# AirCond_P0_V2_0.net
KiCad netlist of a schematic drawn in Altium Designer
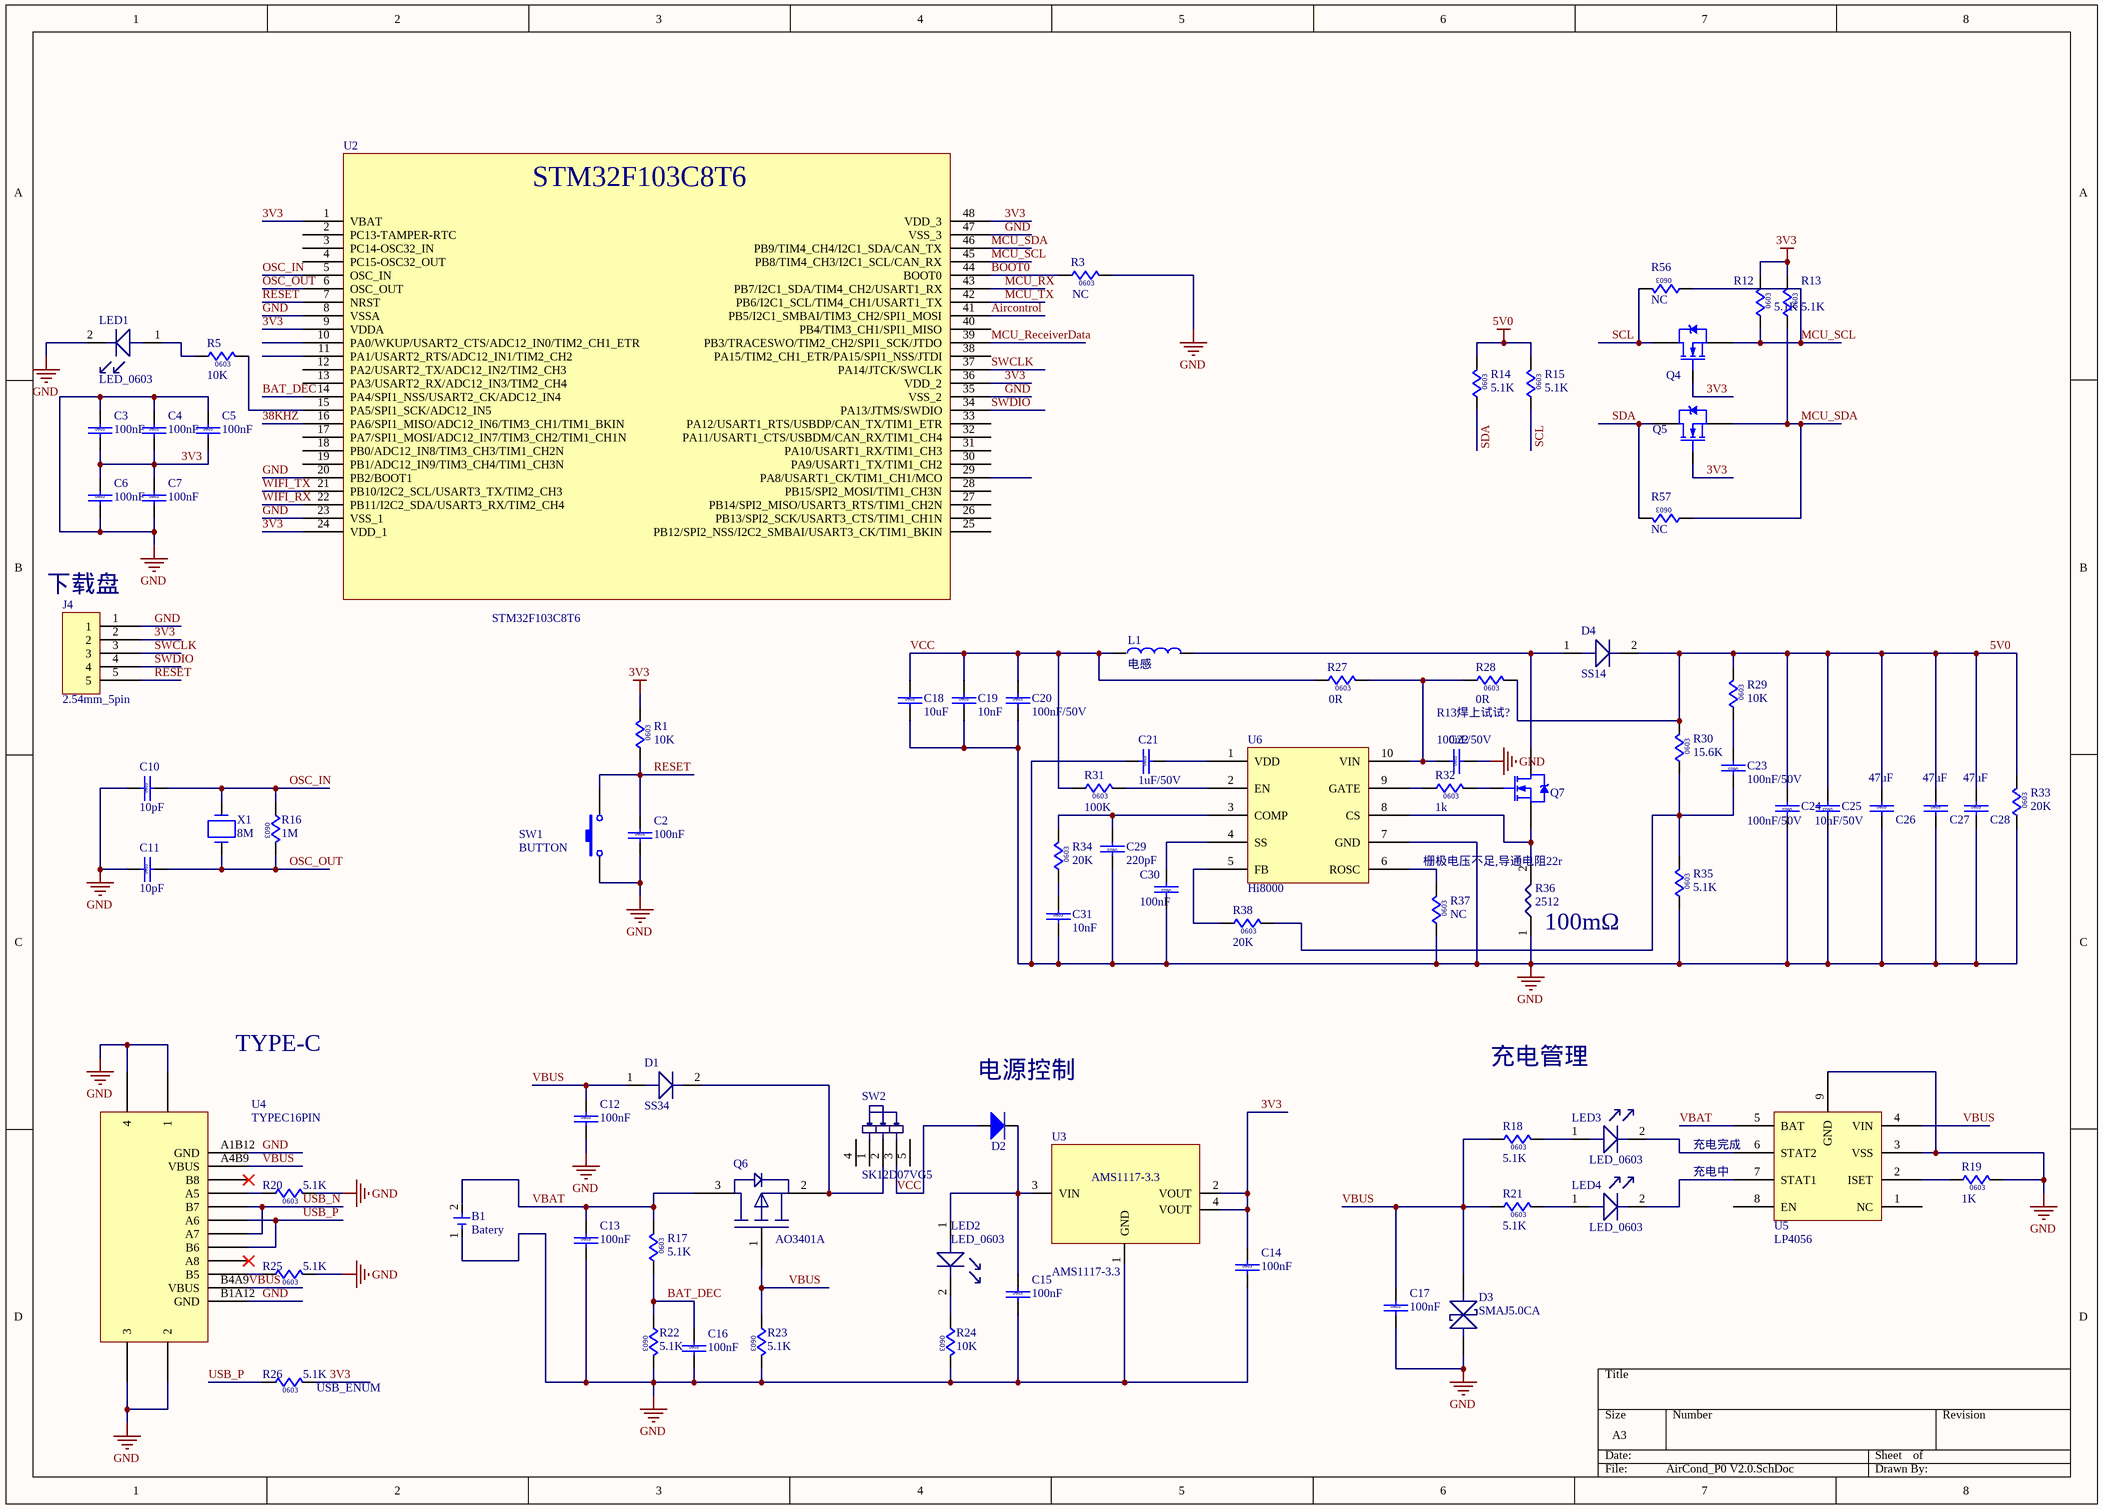
[diagram p0: AirCond_P0 V2.0.SchDoc]

(export (version "E")
  (design (tool "Eeschema 10.0.6"))
  (components
    (comp (ref "B1") (value "Batery") (footprint "BateryBox") (libsource (lib "ZWC") (part "Batery")))
    (comp (ref "C2") (value "100nF") (footprint "0603/CAP") (libsource (lib "ZWC") (part "CAP/0603")))
    (comp (ref "C3") (value "100nF") (footprint "0603/CAP") (libsource (lib "ZWC") (part "CAP/0603")))
    (comp (ref "C4") (value "100nF") (footprint "0603/CAP") (libsource (lib "ZWC") (part "CAP/0603")))
    (comp (ref "C5") (value "100nF") (footprint "0603/CAP") (libsource (lib "ZWC") (part "CAP/0603")))
    (comp (ref "C6") (value "100nF") (footprint "0603/CAP") (libsource (lib "ZWC") (part "CAP/0603")))
    (comp (ref "C7") (value "100nF") (footprint "0603/CAP") (libsource (lib "ZWC") (part "CAP/0603")))
    (comp (ref "C10") (value "10pF") (footprint "0603/CAP") (libsource (lib "ZWC") (part "CAP/0603")))
    (comp (ref "C11") (value "10pF") (footprint "0603/CAP") (libsource (lib "ZWC") (part "CAP/0603")))
    (comp (ref "C12") (value "100nF") (footprint "0603/CAP") (libsource (lib "ZWC") (part "CAP/0603")))
    (comp (ref "C13") (value "100nF") (footprint "0603/CAP") (libsource (lib "ZWC") (part "CAP/0603")))
    (comp (ref "C14") (value "100nF") (footprint "0603/CAP") (libsource (lib "ZWC") (part "CAP/0603")))
    (comp (ref "C15") (value "100nF") (footprint "0603/CAP") (libsource (lib "ZWC") (part "CAP/0603")))
    (comp (ref "C16") (value "100nF") (footprint "0603/CAP") (libsource (lib "ZWC") (part "CAP/0603")))
    (comp (ref "C17") (value "100nF") (footprint "0603/CAP") (libsource (lib "ZWC") (part "CAP/0603")))
    (comp (ref "C18") (value "10uF") (footprint "0603/CAP") (libsource (lib "ZWC") (part "CAP/0603")))
    (comp (ref "C19") (value "10nF") (footprint "0603/CAP") (libsource (lib "ZWC") (part "CAP/0603")))
    (comp (ref "C20") (value "100nF/50V") (footprint "0603/CAP") (libsource (lib "ZWC") (part "CAP/0603")))
    (comp (ref "C21") (value "1uF/50V") (footprint "0603/CAP") (libsource (lib "ZWC") (part "CAP/0603")))
    (comp (ref "C22") (value "100nF/50V") (footprint "0603/CAP") (libsource (lib "ZWC") (part "CAP/0603")))
    (comp (ref "C23") (value "100nF/50V") (footprint "0603/CAP") (libsource (lib "ZWC") (part "CAP/0603")))
    (comp (ref "C24") (value "100nF/50V") (footprint "0603/CAP") (libsource (lib "ZWC") (part "CAP/0603")))
    (comp (ref "C25") (value "10nF/50V") (footprint "0603/CAP") (libsource (lib "ZWC") (part "CAP/0603")))
    (comp (ref "C26") (value "47uF") (footprint "0805 - CAP") (libsource (lib "ZWC") (part "CAP/0805")))
    (comp (ref "C27") (value "47uF") (footprint "0805 - CAP") (libsource (lib "ZWC") (part "CAP/0805")))
    (comp (ref "C28") (value "47uF") (footprint "0805 - CAP") (libsource (lib "ZWC") (part "CAP/0805")))
    (comp (ref "C29") (value "220pF") (footprint "0603/CAP") (libsource (lib "ZWC") (part "CAP/0603")))
    (comp (ref "C30") (value "100nF") (footprint "0603/CAP") (libsource (lib "ZWC") (part "CAP/0603")))
    (comp (ref "C31") (value "10nF") (footprint "0603/CAP") (libsource (lib "ZWC") (part "CAP/0603")))
    (comp (ref "D1")
      (value "SS34")
      (footprint "SMA_L4.3-W2.6-LS5.0-RD")
      (libsource (lib "MySelf") (part "SS34"))
    )
    (comp (ref "D2") (value "S1MFL") (footprint "SOD-123Fl") (libsource (lib "ZWC") (part "S1MFL")))
    (comp (ref "D3")
      (value "SMAJ5.0CA")
      (footprint "DO-214AC(SMA)")
      (libsource (lib "MySelf") (part "SMAJ5.0CA"))
    )
    (comp (ref "D4")
      (value "SS14")
      (footprint "SMA_L4.3-W2.6-LS5.0-RD")
      (libsource (lib "MySelf") (part "SS34"))
    )
    (comp (ref "J4")
      (value "2.54mm_5pin")
      (footprint "2.54mm_5P")
      (libsource (lib "MySelf") (part "2.54mm_5pin"))
    )
    (comp (ref "L1") (value "电感") (footprint "SRP7028A-4R7") (libsource (lib "ZWC") (part "电感")))
    (comp (ref "LED1") (value "LED_0603") (footprint "0603/RES") (libsource (lib "MySelf") (part "LED_0603")))
    (comp (ref "LED2") (value "LED_0603") (footprint "0603/RES") (libsource (lib "MySelf") (part "LED_0603")))
    (comp (ref "LED3") (value "LED_0603") (footprint "0603/RES") (libsource (lib "MySelf") (part "LED_0603")))
    (comp (ref "LED4") (value "LED_0603") (footprint "0603/RES") (libsource (lib "MySelf") (part "LED_0603")))
    (comp (ref "Q4") (value "NMOS") (footprint "SOT-23") (libsource (lib "ZWC") (part "N-MOSE")))
    (comp (ref "Q5") (value "NMOS") (footprint "SOT-23") (libsource (lib "ZWC") (part "N-MOSE")))
    (comp (ref "Q6") (value "AO3401A") (footprint "SOT-23") (libsource (lib "MySelf") (part "AO3401A")))
    (comp (ref "Q7") (value "NMOS") (footprint "SOT-23") (libsource (lib "ZWC") (part "N-MOSE")))
    (comp (ref "R1") (value "10K") (footprint "0603/RES") (libsource (lib "ZWC") (part "RES/0603")))
    (comp (ref "R3") (value "NC") (footprint "0603/RES") (libsource (lib "ZWC") (part "RES/0603")))
    (comp (ref "R5") (value "10K") (footprint "0603/RES") (libsource (lib "ZWC") (part "RES/0603")))
    (comp (ref "R12") (value "5.1K") (footprint "0603/RES") (libsource (lib "ZWC") (part "RES/0603")))
    (comp (ref "R13") (value "5.1K") (footprint "0603/RES") (libsource (lib "ZWC") (part "RES/0603")))
    (comp (ref "R14") (value "5.1K") (footprint "0603/RES") (libsource (lib "ZWC") (part "RES/0603")))
    (comp (ref "R15") (value "5.1K") (footprint "0603/RES") (libsource (lib "ZWC") (part "RES/0603")))
    (comp (ref "R16") (value "1M") (footprint "0603/RES") (libsource (lib "ZWC") (part "RES/0603")))
    (comp (ref "R17") (value "5.1K") (footprint "0603/RES") (libsource (lib "ZWC") (part "RES/0603")))
    (comp (ref "R18") (value "5.1K") (footprint "0603/RES") (libsource (lib "ZWC") (part "RES/0603")))
    (comp (ref "R19") (value "1K") (footprint "0603/RES") (libsource (lib "ZWC") (part "RES/0603")))
    (comp (ref "R20") (value "5.1K") (footprint "0603/RES") (libsource (lib "ZWC") (part "RES/0603")))
    (comp (ref "R21") (value "5.1K") (footprint "0603/RES") (libsource (lib "ZWC") (part "RES/0603")))
    (comp (ref "R22") (value "5.1K") (footprint "0603/RES") (libsource (lib "ZWC") (part "RES/0603")))
    (comp (ref "R23") (value "5.1K") (footprint "0603/RES") (libsource (lib "ZWC") (part "RES/0603")))
    (comp (ref "R24") (value "10K") (footprint "0603/RES") (libsource (lib "ZWC") (part "RES/0603")))
    (comp (ref "R25") (value "5.1K") (footprint "0603/RES") (libsource (lib "ZWC") (part "RES/0603")))
    (comp (ref "R26") (value "5.1K") (footprint "0603/RES") (libsource (lib "ZWC") (part "RES/0603")))
    (comp (ref "R27") (value "0R") (footprint "0603/RES") (libsource (lib "ZWC") (part "RES/0603")))
    (comp (ref "R28") (value "0R") (footprint "0603/RES") (libsource (lib "ZWC") (part "RES/0603")))
    (comp (ref "R29") (value "10K") (footprint "0603/RES") (libsource (lib "ZWC") (part "RES/0603")))
    (comp (ref "R30") (value "15.6K") (footprint "0603/RES") (libsource (lib "ZWC") (part "RES/0603")))
    (comp (ref "R31") (value "100K") (footprint "0603/RES") (libsource (lib "ZWC") (part "RES/0603")))
    (comp (ref "R32") (value "1k") (footprint "0603/RES") (libsource (lib "ZWC") (part "RES/0603")))
    (comp (ref "R33") (value "20K") (footprint "0603/RES") (libsource (lib "ZWC") (part "RES/0603")))
    (comp (ref "R34") (value "20K") (footprint "0603/RES") (libsource (lib "ZWC") (part "RES/0603")))
    (comp (ref "R35") (value "5.1K") (footprint "0603/RES") (libsource (lib "ZWC") (part "RES/0603")))
    (comp (ref "R36") (value "2512") (footprint "2512") (libsource (lib "MySelf") (part "2512")))
    (comp (ref "R37") (value "NC") (footprint "0603/RES") (libsource (lib "ZWC") (part "RES/0603")))
    (comp (ref "R38") (value "20K") (footprint "0603/RES") (libsource (lib "ZWC") (part "RES/0603")))
    (comp (ref "R56") (value "NC") (footprint "0603/RES") (libsource (lib "ZWC") (part "RES/0603")))
    (comp (ref "R57") (value "NC") (footprint "0603/RES") (libsource (lib "ZWC") (part "RES/0603")))
    (comp (ref "SW1") (value "BUTTON") (footprint "Key-D8mm") (libsource (lib "ZWC") (part "BUTTON_1")))
    (comp (ref "SW2")
      (value "SK12D07VG5")
      (footprint "SK12D07VG5")
      (libsource (lib "MySelf") (part "SK12D07VG5"))
    )
    (comp (ref "U2")
      (value "STM32F103C8T6")
      (footprint "LQFP48-STM32")
      (description "STM32F103")
      (libsource (lib "MySelf") (part "STM32F103C8T6"))
    )
    (comp (ref "U3")
      (value "AMS1117-3.3")
      (footprint "AMS1117-3.3")
      (libsource (lib "ZWC") (part "AMS1117-3.3"))
    )
    (comp (ref "U4")
      (value "TYPEC16PIN")
      (footprint "Type-C 16PIN")
      (libsource (lib "MySelf") (part "TYPEC16PIN"))
    )
    (comp (ref "U5") (value "LP4056") (footprint "ESOP-8") (libsource (lib "MySelf") (part "LP4056")))
    (comp (ref "U6") (value "Hi8000") (footprint "ESSOP10") (libsource (lib "MySelf") (part "Hi8000")))
    (comp (ref "X1") (value "8M") (footprint "两脚晶振") (libsource (lib "ZWC") (part "两脚 晶振")))
  )
  (nets
    (net (code "1") (name "/38KHZ") (class "Default")
      (node (ref "U2") (pin "16") (pinfunction "PA6/SPI1_MISO/ADC12_IN6/TIM3_CH1/TIM1_BKIN_16") (pintype "passive"))
    )
    (net (code "2") (name "/Aircontrol") (class "Default")
      (node (ref "U2") (pin "41") (pinfunction "PB5/I2C1_SMBAI/TIM3_CH2/SPI1_MOSI_41") (pintype "passive"))
    )
    (net (code "3") (name "/BAT_DEC") (class "Default")
      (node (ref "C16") (pin "1") (pinfunction "1_1") (pintype "passive"))
      (node (ref "R17") (pin "1") (pinfunction "1_1") (pintype "passive"))
      (node (ref "R22") (pin "1") (pinfunction "1_1") (pintype "passive"))
      (node (ref "U2") (pin "14") (pinfunction "PA4/SPI1_NSS/USART2_CK/ADC12_IN4_14") (pintype "passive"))
    )
    (net (code "4") (name "/BOOT0") (class "Default")
      (node (ref "R3") (pin "1") (pinfunction "1_1") (pintype "passive"))
      (node (ref "U2") (pin "44") (pinfunction "BOOT0_44") (pintype "passive"))
    )
    (net (code "5") (name "/MCU_RX") (class "Default")
      (node (ref "U2") (pin "43") (pinfunction "PB7/I2C1_SDA/TIM4_CH2/USART1_RX_43") (pintype "passive"))
    )
    (net (code "6") (name "/MCU_ReceiverData") (class "Default")
      (node (ref "U2") (pin "39") (pinfunction "PB3/TRACESWO/TIM2_CH2/SPI1_SCK/JTDO_39") (pintype "passive"))
    )
    (net (code "7") (name "/MCU_SCL") (class "Default")
      (node (ref "Q4") (pin "2") (pinfunction "S_2") (pintype "passive"))
      (node (ref "R12") (pin "1") (pinfunction "1_1") (pintype "passive"))
      (node (ref "R56") (pin "1") (pinfunction "1_1") (pintype "passive"))
      (node (ref "U2") (pin "45") (pinfunction "PB8/TIM4_CH3/I2C1_SCL/CAN_RX_45") (pintype "passive"))
    )
    (net (code "8") (name "/MCU_SDA") (class "Default")
      (node (ref "Q5") (pin "2") (pinfunction "S_2") (pintype "passive"))
      (node (ref "R13") (pin "1") (pinfunction "1_1") (pintype "passive"))
      (node (ref "R57") (pin "1") (pinfunction "1_1") (pintype "passive"))
      (node (ref "U2") (pin "46") (pinfunction "PB9/TIM4_CH4/I2C1_SDA/CAN_TX_46") (pintype "passive"))
    )
    (net (code "9") (name "/MCU_TX") (class "Default")
      (node (ref "U2") (pin "42") (pinfunction "PB6/I2C1_SCL/TIM4_CH1/USART1_TX_42") (pintype "passive"))
    )
    (net (code "10") (name "/OSC_IN") (class "Default")
      (node (ref "C10") (pin "2") (pinfunction "2_2") (pintype "passive"))
      (node (ref "R16") (pin "1") (pinfunction "1_1") (pintype "passive"))
      (node (ref "U2") (pin "5") (pinfunction "OSC_IN_5") (pintype "passive"))
      (node (ref "X1") (pin "2") (pinfunction "2_2") (pintype "passive"))
    )
    (net (code "11") (name "/OSC_OUT") (class "Default")
      (node (ref "C11") (pin "2") (pinfunction "2_2") (pintype "passive"))
      (node (ref "R16") (pin "2") (pinfunction "2_2") (pintype "passive"))
      (node (ref "U2") (pin "6") (pinfunction "OSC_OUT_6") (pintype "passive"))
      (node (ref "X1") (pin "1") (pinfunction "1_1") (pintype "passive"))
    )
    (net (code "12") (name "/RESET") (class "Default")
      (node (ref "C2") (pin "1") (pinfunction "1_1") (pintype "passive"))
      (node (ref "J4") (pin "5") (pinfunction "5_5") (pintype "passive"))
      (node (ref "R1") (pin "1") (pinfunction "1_1") (pintype "passive"))
      (node (ref "SW1") (pin "2") (pinfunction "2_2") (pintype "passive"))
      (node (ref "U2") (pin "7") (pinfunction "NRST_7") (pintype "passive"))
    )
    (net (code "13") (name "/SCL") (class "Default")
      (node (ref "Q4") (pin "3") (pinfunction "D_3") (pintype "passive"))
      (node (ref "R15") (pin "1") (pinfunction "1_1") (pintype "passive"))
      (node (ref "R56") (pin "2") (pinfunction "2_2") (pintype "passive"))
    )
    (net (code "14") (name "/SDA") (class "Default")
      (node (ref "Q5") (pin "3") (pinfunction "D_3") (pintype "passive"))
      (node (ref "R14") (pin "1") (pinfunction "1_1") (pintype "passive"))
      (node (ref "R57") (pin "2") (pinfunction "2_2") (pintype "passive"))
    )
    (net (code "15") (name "/SWCLK") (class "Default")
      (node (ref "J4") (pin "3") (pinfunction "3_3") (pintype "passive"))
      (node (ref "U2") (pin "37") (pinfunction "PA14/JTCK/SWCLK_37") (pintype "passive"))
    )
    (net (code "16") (name "/SWDIO") (class "Default")
      (node (ref "J4") (pin "4") (pinfunction "4_4") (pintype "passive"))
      (node (ref "U2") (pin "34") (pinfunction "PA13/JTMS/SWDIO_34") (pintype "passive"))
    )
    (net (code "17") (name "/USB_N") (class "Default")
      (node (ref "U4") (pin "A7") (pinfunction "A7_A7") (pintype "passive"))
      (node (ref "U4") (pin "B7") (pinfunction "B7_B7") (pintype "passive"))
    )
    (net (code "18") (name "/USB_P") (class "Default")
      (node (ref "R26") (pin "1") (pinfunction "1_1") (pintype "passive"))
      (node (ref "U4") (pin "A6") (pinfunction "A6_A6") (pintype "passive"))
      (node (ref "U4") (pin "B6") (pinfunction "B6_B6") (pintype "passive"))
    )
    (net (code "19") (name "/VBAT") (class "Default")
      (node (ref "B1") (pin "2") (pinfunction "+_2") (pintype "passive"))
      (node (ref "C13") (pin "1") (pinfunction "1_1") (pintype "passive"))
      (node (ref "Q6") (pin "3") (pinfunction "3_3") (pintype "passive"))
      (node (ref "R17") (pin "2") (pinfunction "2_2") (pintype "passive"))
      (node (ref "U5") (pin "5") (pinfunction "BAT_5") (pintype "passive"))
    )
    (net (code "20") (name "/VBUS") (class "Default")
      (node (ref "C12") (pin "1") (pinfunction "1_1") (pintype "passive"))
      (node (ref "C17") (pin "1") (pinfunction "1_1") (pintype "passive"))
      (node (ref "D1") (pin "1") (pinfunction "1_1") (pintype "passive"))
      (node (ref "D3") (pin "1") (pinfunction "1_1") (pintype "passive"))
      (node (ref "Q6") (pin "1") (pinfunction "1_1") (pintype "passive"))
      (node (ref "R18") (pin "1") (pinfunction "1_1") (pintype "passive"))
      (node (ref "R21") (pin "1") (pinfunction "1_1") (pintype "passive"))
      (node (ref "R23") (pin "1") (pinfunction "1_1") (pintype "passive"))
      (node (ref "U4") (pin "A4B9") (pinfunction "VBUS_A4B9") (pintype "passive"))
      (node (ref "U4") (pin "B4A9") (pinfunction "VBUS_B4A9") (pintype "passive"))
      (node (ref "U5") (pin "4") (pinfunction "VIN_4") (pintype "passive"))
    )
    (net (code "21") (name "/VCC") (class "Default")
      (node (ref "C18") (pin "1") (pinfunction "1_1") (pintype "passive"))
      (node (ref "C19") (pin "1") (pinfunction "1_1") (pintype "passive"))
      (node (ref "C20") (pin "1") (pinfunction "1_1") (pintype "passive"))
      (node (ref "D2") (pin "1") (pintype "passive"))
      (node (ref "L1") (pin "1") (pinfunction "1_1") (pintype "passive"))
      (node (ref "R27") (pin "1") (pinfunction "1_1") (pintype "passive"))
      (node (ref "R31") (pin "1") (pinfunction "1_1") (pintype "passive"))
      (node (ref "SW2") (pin "3") (pinfunction "3_3") (pintype "passive"))
    )
    (net (code "22") (name "/WIFI_RX") (class "Default")
      (node (ref "U2") (pin "22") (pinfunction "PB11/I2C2_SDA/USART3_RX/TIM2_CH4_22") (pintype "passive"))
    )
    (net (code "23") (name "/WIFI_TX") (class "Default")
      (node (ref "U2") (pin "21") (pinfunction "PB10/I2C2_SCL/USART3_TX/TIM2_CH3_21") (pintype "passive"))
    )
    (net (code "24") (name "3V3") (class "Default")
      (node (ref "C14") (pin "1") (pinfunction "1_1") (pintype "passive"))
      (node (ref "C3") (pin "2") (pinfunction "2_2") (pintype "passive"))
      (node (ref "C4") (pin "2") (pinfunction "2_2") (pintype "passive"))
      (node (ref "C5") (pin "2") (pinfunction "2_2") (pintype "passive"))
      (node (ref "C6") (pin "1") (pinfunction "1_1") (pintype "passive"))
      (node (ref "C7") (pin "1") (pinfunction "1_1") (pintype "passive"))
      (node (ref "J4") (pin "2") (pinfunction "2_2") (pintype "passive"))
      (node (ref "Q4") (pin "1") (pinfunction "G_1") (pintype "passive"))
      (node (ref "Q5") (pin "1") (pinfunction "G_1") (pintype "passive"))
      (node (ref "R1") (pin "2") (pinfunction "2_2") (pintype "passive"))
      (node (ref "R12") (pin "2") (pinfunction "2_2") (pintype "passive"))
      (node (ref "R13") (pin "2") (pinfunction "2_2") (pintype "passive"))
      (node (ref "R26") (pin "2") (pinfunction "2_2") (pintype "passive"))
      (node (ref "U2") (pin "1") (pinfunction "VBAT_1") (pintype "passive"))
      (node (ref "U2") (pin "24") (pinfunction "VDD_1_24") (pintype "passive"))
      (node (ref "U2") (pin "36") (pinfunction "VDD_2_36") (pintype "passive"))
      (node (ref "U2") (pin "48") (pinfunction "VDD_3_48") (pintype "passive"))
      (node (ref "U2") (pin "9") (pinfunction "VDDA_9") (pintype "passive"))
      (node (ref "U3") (pin "2") (pinfunction "VOUT_2") (pintype "passive"))
      (node (ref "U3") (pin "4") (pinfunction "VOUT_4") (pintype "passive"))
    )
    (net (code "25") (name "5V0") (class "Default")
      (node (ref "C24") (pin "2") (pinfunction "2_2") (pintype "passive"))
      (node (ref "C25") (pin "2") (pinfunction "2_2") (pintype "passive"))
      (node (ref "C26") (pin "1") (pinfunction "1_1") (pintype "passive"))
      (node (ref "C27") (pin "1") (pinfunction "1_1") (pintype "passive"))
      (node (ref "C28") (pin "1") (pinfunction "1_1") (pintype "passive"))
      (node (ref "D4") (pin "2") (pinfunction "2_2") (pintype "passive"))
      (node (ref "R14") (pin "2") (pinfunction "2_2") (pintype "passive"))
      (node (ref "R15") (pin "2") (pinfunction "2_2") (pintype "passive"))
      (node (ref "R28") (pin "2") (pinfunction "2_2") (pintype "passive"))
      (node (ref "R29") (pin "2") (pinfunction "2_2") (pintype "passive"))
      (node (ref "R30") (pin "2") (pinfunction "2_2") (pintype "passive"))
      (node (ref "R33") (pin "2") (pinfunction "2_2") (pintype "passive"))
    )
    (net (code "26") (name "GND") (class "Default")
      (node (ref "B1") (pin "1") (pinfunction "-_1") (pintype "passive"))
      (node (ref "C10") (pin "1") (pinfunction "1_1") (pintype "passive"))
      (node (ref "C11") (pin "1") (pinfunction "1_1") (pintype "passive"))
      (node (ref "C12") (pin "2") (pinfunction "2_2") (pintype "passive"))
      (node (ref "C13") (pin "2") (pinfunction "2_2") (pintype "passive"))
      (node (ref "C14") (pin "2") (pinfunction "2_2") (pintype "passive"))
      (node (ref "C15") (pin "2") (pinfunction "2_2") (pintype "passive"))
      (node (ref "C16") (pin "2") (pinfunction "2_2") (pintype "passive"))
      (node (ref "C17") (pin "2") (pinfunction "2_2") (pintype "passive"))
      (node (ref "C18") (pin "2") (pinfunction "2_2") (pintype "passive"))
      (node (ref "C19") (pin "2") (pinfunction "2_2") (pintype "passive"))
      (node (ref "C2") (pin "2") (pinfunction "2_2") (pintype "passive"))
      (node (ref "C20") (pin "2") (pinfunction "2_2") (pintype "passive"))
      (node (ref "C21") (pin "1") (pinfunction "1_1") (pintype "passive"))
      (node (ref "C22") (pin "2") (pinfunction "2_2") (pintype "passive"))
      (node (ref "C24") (pin "1") (pinfunction "1_1") (pintype "passive"))
      (node (ref "C25") (pin "1") (pinfunction "1_1") (pintype "passive"))
      (node (ref "C26") (pin "2") (pinfunction "2_2") (pintype "passive"))
      (node (ref "C27") (pin "2") (pinfunction "2_2") (pintype "passive"))
      (node (ref "C28") (pin "2") (pinfunction "2_2") (pintype "passive"))
      (node (ref "C29") (pin "1") (pinfunction "1_1") (pintype "passive"))
      (node (ref "C3") (pin "1") (pinfunction "1_1") (pintype "passive"))
      (node (ref "C30") (pin "1") (pinfunction "1_1") (pintype "passive"))
      (node (ref "C31") (pin "2") (pinfunction "2_2") (pintype "passive"))
      (node (ref "C4") (pin "1") (pinfunction "1_1") (pintype "passive"))
      (node (ref "C5") (pin "1") (pinfunction "1_1") (pintype "passive"))
      (node (ref "C6") (pin "2") (pinfunction "2_2") (pintype "passive"))
      (node (ref "C7") (pin "2") (pinfunction "2_2") (pintype "passive"))
      (node (ref "D3") (pin "2") (pinfunction "2_2") (pintype "passive"))
      (node (ref "J4") (pin "1") (pinfunction "1_1") (pintype "passive"))
      (node (ref "LED1") (pin "2") (pinfunction "2_2") (pintype "passive"))
      (node (ref "R19") (pin "2") (pinfunction "2_2") (pintype "passive"))
      (node (ref "R20") (pin "2") (pinfunction "2_2") (pintype "passive"))
      (node (ref "R22") (pin "2") (pinfunction "2_2") (pintype "passive"))
      (node (ref "R23") (pin "2") (pinfunction "2_2") (pintype "passive"))
      (node (ref "R24") (pin "2") (pinfunction "2_2") (pintype "passive"))
      (node (ref "R25") (pin "2") (pinfunction "2_2") (pintype "passive"))
      (node (ref "R3") (pin "2") (pinfunction "2_2") (pintype "passive"))
      (node (ref "R33") (pin "1") (pinfunction "1_1") (pintype "passive"))
      (node (ref "R35") (pin "1") (pinfunction "1_1") (pintype "passive"))
      (node (ref "R36") (pin "1") (pinfunction "1_1") (pintype "passive"))
      (node (ref "R37") (pin "1") (pinfunction "1_1") (pintype "passive"))
      (node (ref "SW1") (pin "1") (pinfunction "1_1") (pintype "passive"))
      (node (ref "U2") (pin "20") (pinfunction "PB2/BOOT1_20") (pintype "passive"))
      (node (ref "U2") (pin "23") (pinfunction "VSS_1_23") (pintype "passive"))
      (node (ref "U2") (pin "35") (pinfunction "VSS_2_35") (pintype "passive"))
      (node (ref "U2") (pin "47") (pinfunction "VSS_3_47") (pintype "passive"))
      (node (ref "U2") (pin "8") (pinfunction "VSSA_8") (pintype "passive"))
      (node (ref "U3") (pin "1") (pinfunction "GND_1") (pintype "passive"))
      (node (ref "U4") (pin "1") (pinfunction "1_1") (pintype "passive"))
      (node (ref "U4") (pin "2") (pinfunction "2_2") (pintype "passive"))
      (node (ref "U4") (pin "3") (pinfunction "3_3") (pintype "passive"))
      (node (ref "U4") (pin "4") (pinfunction "4_4") (pintype "passive"))
      (node (ref "U4") (pin "A1B12") (pinfunction "GND_A1B12") (pintype "passive"))
      (node (ref "U4") (pin "B1A12") (pinfunction "GND_B1A12") (pintype "passive"))
      (node (ref "U5") (pin "3") (pinfunction "VSS_3") (pintype "passive"))
      (node (ref "U5") (pin "9") (pinfunction "GND_9") (pintype "passive"))
      (node (ref "U6") (pin "7") (pinfunction "GND_7") (pintype "passive"))
    )
    (net (code "27") (name "Net-(C23-Pad1)") (class "Default")
      (node (ref "C23") (pin "1") (pinfunction "1_1") (pintype "passive"))
      (node (ref "R30") (pin "1") (pinfunction "1_1") (pintype "passive"))
      (node (ref "R35") (pin "2") (pinfunction "2_2") (pintype "passive"))
      (node (ref "R38") (pin "2") (pinfunction "2_2") (pintype "passive"))
    )
    (net (code "28") (name "Net-(C23-Pad2)") (class "Default")
      (node (ref "C23") (pin "2") (pinfunction "2_2") (pintype "passive"))
      (node (ref "R29") (pin "1") (pinfunction "1_1") (pintype "passive"))
    )
    (net (code "29") (name "Net-(C31-Pad1)") (class "Default")
      (node (ref "C31") (pin "1") (pinfunction "1_1") (pintype "passive"))
      (node (ref "R34") (pin "1") (pinfunction "1_1") (pintype "passive"))
    )
    (net (code "30") (name "Net-(D1-Pad2)") (class "Default")
      (node (ref "D1") (pin "2") (pinfunction "2_2") (pintype "passive"))
      (node (ref "Q6") (pin "2") (pinfunction "2_2") (pintype "passive"))
      (node (ref "SW2") (pin "2") (pinfunction "2_2") (pintype "passive"))
    )
    (net (code "31") (name "Net-(LED1-Pad1)") (class "Default")
      (node (ref "LED1") (pin "1") (pinfunction "1_1") (pintype "passive"))
      (node (ref "R5") (pin "1") (pinfunction "1_1") (pintype "passive"))
    )
    (net (code "32") (name "Net-(LED2-Pad2)") (class "Default")
      (node (ref "LED2") (pin "2") (pinfunction "2_2") (pintype "passive"))
      (node (ref "R24") (pin "1") (pinfunction "1_1") (pintype "passive"))
    )
    (net (code "33") (name "Net-(LED3-Pad1)") (class "Default")
      (node (ref "LED3") (pin "1") (pinfunction "1_1") (pintype "passive"))
      (node (ref "R18") (pin "2") (pinfunction "2_2") (pintype "passive"))
    )
    (net (code "34") (name "Net-(LED4-Pad1)") (class "Default")
      (node (ref "LED4") (pin "1") (pinfunction "1_1") (pintype "passive"))
      (node (ref "R21") (pin "2") (pinfunction "2_2") (pintype "passive"))
    )
    (net (code "35") (name "Net-(Q7-D)") (class "Default")
      (node (ref "D4") (pin "1") (pinfunction "1_1") (pintype "passive"))
      (node (ref "L1") (pin "2") (pinfunction "2_2") (pintype "passive"))
      (node (ref "Q7") (pin "3") (pinfunction "D_3") (pintype "passive"))
    )
    (net (code "36") (name "Net-(Q7-G)") (class "Default")
      (node (ref "Q7") (pin "1") (pinfunction "G_1") (pintype "passive"))
      (node (ref "R32") (pin "2") (pinfunction "2_2") (pintype "passive"))
    )
    (net (code "37") (name "Net-(Q7-S)") (class "Default")
      (node (ref "Q7") (pin "2") (pinfunction "S_2") (pintype "passive"))
      (node (ref "R36") (pin "2") (pinfunction "2_2") (pintype "passive"))
      (node (ref "U6") (pin "8") (pinfunction "CS_8") (pintype "passive"))
    )
    (net (code "38") (name "Net-(R20-Pad1)") (class "Default")
      (node (ref "R20") (pin "1") (pinfunction "1_1") (pintype "passive"))
      (node (ref "U4") (pin "A5") (pinfunction "A5_A5") (pintype "passive"))
    )
    (net (code "39") (name "Net-(R25-Pad1)") (class "Default")
      (node (ref "R25") (pin "1") (pinfunction "1_1") (pintype "passive"))
      (node (ref "U4") (pin "B5") (pinfunction "B5_B5") (pintype "passive"))
    )
    (net (code "40") (name "Net-(U2-PA5{slash}SPI1_SCK{slash}ADC12_IN5)") (class "Default")
      (node (ref "R5") (pin "2") (pinfunction "2_2") (pintype "passive"))
      (node (ref "U2") (pin "15") (pinfunction "PA5/SPI1_SCK/ADC12_IN5_15") (pintype "passive"))
    )
    (net (code "41") (name "Net-(U3-VIN)") (class "Default")
      (node (ref "C15") (pin "1") (pinfunction "1_1") (pintype "passive"))
      (node (ref "D2") (pin "2") (pintype "passive"))
      (node (ref "LED2") (pin "1") (pinfunction "1_1") (pintype "passive"))
      (node (ref "U3") (pin "3") (pinfunction "VIN_3") (pintype "passive"))
    )
    (net (code "42") (name "Net-(U5-ISET)") (class "Default")
      (node (ref "R19") (pin "1") (pinfunction "1_1") (pintype "passive"))
      (node (ref "U5") (pin "2") (pinfunction "ISET_2") (pintype "passive"))
    )
    (net (code "43") (name "Net-(U5-STAT1)") (class "Default")
      (node (ref "LED4") (pin "2") (pinfunction "2_2") (pintype "passive"))
      (node (ref "U5") (pin "7") (pinfunction "STAT1_7") (pintype "passive"))
    )
    (net (code "44") (name "Net-(U5-STAT2)") (class "Default")
      (node (ref "LED3") (pin "2") (pinfunction "2_2") (pintype "passive"))
      (node (ref "U5") (pin "6") (pinfunction "STAT2_6") (pintype "passive"))
    )
    (net (code "45") (name "Net-(U6-COMP)") (class "Default")
      (node (ref "C29") (pin "2") (pinfunction "2_2") (pintype "passive"))
      (node (ref "R34") (pin "2") (pinfunction "2_2") (pintype "passive"))
      (node (ref "U6") (pin "3") (pinfunction "COMP_3") (pintype "passive"))
    )
    (net (code "46") (name "Net-(U6-EN)") (class "Default")
      (node (ref "R31") (pin "2") (pinfunction "2_2") (pintype "passive"))
      (node (ref "U6") (pin "2") (pinfunction "EN_2") (pintype "passive"))
    )
    (net (code "47") (name "Net-(U6-FB)") (class "Default")
      (node (ref "R38") (pin "1") (pinfunction "1_1") (pintype "passive"))
      (node (ref "U6") (pin "5") (pinfunction "FB_5") (pintype "passive"))
    )
    (net (code "48") (name "Net-(U6-GATE)") (class "Default")
      (node (ref "R32") (pin "1") (pinfunction "1_1") (pintype "passive"))
      (node (ref "U6") (pin "9") (pinfunction "GATE_9") (pintype "passive"))
    )
    (net (code "49") (name "Net-(U6-ROSC)") (class "Default")
      (node (ref "R37") (pin "2") (pinfunction "2_2") (pintype "passive"))
      (node (ref "U6") (pin "6") (pinfunction "ROSC_6") (pintype "passive"))
    )
    (net (code "50") (name "Net-(U6-SS)") (class "Default")
      (node (ref "C30") (pin "2") (pinfunction "2_2") (pintype "passive"))
      (node (ref "U6") (pin "4") (pinfunction "SS_4") (pintype "passive"))
    )
    (net (code "51") (name "Net-(U6-VDD)") (class "Default")
      (node (ref "C21") (pin "2") (pinfunction "2_2") (pintype "passive"))
      (node (ref "U6") (pin "1") (pinfunction "VDD_1") (pintype "passive"))
    )
    (net (code "52") (name "Net-(U6-VIN)") (class "Default")
      (node (ref "C22") (pin "1") (pinfunction "1_1") (pintype "passive"))
      (node (ref "R27") (pin "2") (pinfunction "2_2") (pintype "passive"))
      (node (ref "R28") (pin "1") (pinfunction "1_1") (pintype "passive"))
      (node (ref "U6") (pin "10") (pinfunction "VIN_10") (pintype "passive"))
    )
    (net (code "53") (name "unconnected-(SW2-Pad1)") (class "Default")
      (node (ref "SW2") (pin "1") (pinfunction "1_1") (pintype "passive"))
    )
    (net (code "54") (name "unconnected-(SW2-Pad4)") (class "Default")
      (node (ref "SW2") (pin "4") (pinfunction "4_4") (pintype "passive"))
    )
    (net (code "55") (name "unconnected-(SW2-Pad5)") (class "Default")
      (node (ref "SW2") (pin "5") (pinfunction "5_5") (pintype "passive"))
    )
    (net (code "56") (name "unconnected-(U2-PA0{slash}WKUP{slash}USART2_CTS{slash}ADC12_IN0{slash}TIM2_CH1_ETR-Pad10)") (class "Default")
      (node (ref "U2") (pin "10") (pinfunction "PA0/WKUP/USART2_CTS/ADC12_IN0/TIM2_CH1_ETR_10") (pintype "passive"))
    )
    (net (code "57") (name "unconnected-(U2-PA1{slash}USART2_RTS{slash}ADC12_IN1{slash}TIM2_CH2-Pad11)") (class "Default")
      (node (ref "U2") (pin "11") (pinfunction "PA1/USART2_RTS/ADC12_IN1/TIM2_CH2_11") (pintype "passive"))
    )
    (net (code "58") (name "unconnected-(U2-PA2{slash}USART2_TX{slash}ADC12_IN2{slash}TIM2_CH3-Pad12)") (class "Default")
      (node (ref "U2") (pin "12") (pinfunction "PA2/USART2_TX/ADC12_IN2/TIM2_CH3_12") (pintype "passive"))
    )
    (net (code "59") (name "unconnected-(U2-PA3{slash}USART2_RX{slash}ADC12_IN3{slash}TIM2_CH4-Pad13)") (class "Default")
      (node (ref "U2") (pin "13") (pinfunction "PA3/USART2_RX/ADC12_IN3/TIM2_CH4_13") (pintype "passive"))
    )
    (net (code "60") (name "unconnected-(U2-PA7{slash}SPI1_MOSI{slash}ADC12_IN7{slash}TIM3_CH2{slash}TIM1_CH1N-Pad17)") (class "Default")
      (node (ref "U2") (pin "17") (pinfunction "PA7/SPI1_MOSI/ADC12_IN7/TIM3_CH2/TIM1_CH1N_17") (pintype "passive"))
    )
    (net (code "61") (name "unconnected-(U2-PA8{slash}USART1_CK{slash}TIM1_CH1{slash}MCO-Pad29)") (class "Default")
      (node (ref "U2") (pin "29") (pinfunction "PA8/USART1_CK/TIM1_CH1/MCO_29") (pintype "passive"))
    )
    (net (code "62") (name "unconnected-(U2-PA9{slash}USART1_TX{slash}TIM1_CH2-Pad30)") (class "Default")
      (node (ref "U2") (pin "30") (pinfunction "PA9/USART1_TX/TIM1_CH2_30") (pintype "passive"))
    )
    (net (code "63") (name "unconnected-(U2-PA10{slash}USART1_RX{slash}TIM1_CH3-Pad31)") (class "Default")
      (node (ref "U2") (pin "31") (pinfunction "PA10/USART1_RX/TIM1_CH3_31") (pintype "passive"))
    )
    (net (code "64") (name "unconnected-(U2-PA11{slash}USART1_CTS{slash}USBDM{slash}CAN_RX{slash}TIM1_CH4-Pad32)") (class "Default")
      (node (ref "U2") (pin "32") (pinfunction "PA11/USART1_CTS/USBDM/CAN_RX/TIM1_CH4_32") (pintype "passive"))
    )
    (net (code "65") (name "unconnected-(U2-PA12{slash}USART1_RTS{slash}USBDP{slash}CAN_TX{slash}TIM1_ETR-Pad33)") (class "Default")
      (node (ref "U2") (pin "33") (pinfunction "PA12/USART1_RTS/USBDP/CAN_TX/TIM1_ETR_33") (pintype "passive"))
    )
    (net (code "66") (name "unconnected-(U2-PA15{slash}TIM2_CH1_ETR{slash}PA15{slash}SPI1_NSS{slash}JTDI-Pad38)") (class "Default")
      (node (ref "U2") (pin "38") (pinfunction "PA15/TIM2_CH1_ETR/PA15/SPI1_NSS/JTDI_38") (pintype "passive"))
    )
    (net (code "67") (name "unconnected-(U2-PB0{slash}ADC12_IN8{slash}TIM3_CH3{slash}TIM1_CH2N-Pad18)") (class "Default")
      (node (ref "U2") (pin "18") (pinfunction "PB0/ADC12_IN8/TIM3_CH3/TIM1_CH2N_18") (pintype "passive"))
    )
    (net (code "68") (name "unconnected-(U2-PB1{slash}ADC12_IN9{slash}TIM3_CH4{slash}TIM1_CH3N-Pad19)") (class "Default")
      (node (ref "U2") (pin "19") (pinfunction "PB1/ADC12_IN9/TIM3_CH4/TIM1_CH3N_19") (pintype "passive"))
    )
    (net (code "69") (name "unconnected-(U2-PB4{slash}TIM3_CH1{slash}SPI1_MISO-Pad40)") (class "Default")
      (node (ref "U2") (pin "40") (pinfunction "PB4/TIM3_CH1/SPI1_MISO_40") (pintype "passive"))
    )
    (net (code "70") (name "unconnected-(U2-PB12{slash}SPI2_NSS{slash}I2C2_SMBAI{slash}USART3_CK{slash}TIM1_BKIN-Pad25)") (class "Default")
      (node (ref "U2") (pin "25") (pinfunction "PB12/SPI2_NSS/I2C2_SMBAI/USART3_CK/TIM1_BKIN_25") (pintype "passive"))
    )
    (net (code "71") (name "unconnected-(U2-PB13{slash}SPI2_SCK{slash}USART3_CTS{slash}TIM1_CH1N-Pad26)") (class "Default")
      (node (ref "U2") (pin "26") (pinfunction "PB13/SPI2_SCK/USART3_CTS/TIM1_CH1N_26") (pintype "passive"))
    )
    (net (code "72") (name "unconnected-(U2-PB14{slash}SPI2_MISO{slash}USART3_RTS{slash}TIM1_CH2N-Pad27)") (class "Default")
      (node (ref "U2") (pin "27") (pinfunction "PB14/SPI2_MISO/USART3_RTS/TIM1_CH2N_27") (pintype "passive"))
    )
    (net (code "73") (name "unconnected-(U2-PB15{slash}SPI2_MOSI{slash}TIM1_CH3N-Pad28)") (class "Default")
      (node (ref "U2") (pin "28") (pinfunction "PB15/SPI2_MOSI/TIM1_CH3N_28") (pintype "passive"))
    )
    (net (code "74") (name "unconnected-(U2-PC13-TAMPER-RTC-Pad2)") (class "Default")
      (node (ref "U2") (pin "2") (pinfunction "PC13-TAMPER-RTC_2") (pintype "passive"))
    )
    (net (code "75") (name "unconnected-(U2-PC14-OSC32_IN-Pad3)") (class "Default")
      (node (ref "U2") (pin "3") (pinfunction "PC14-OSC32_IN_3") (pintype "passive"))
    )
    (net (code "76") (name "unconnected-(U2-PC15-OSC32_OUT-Pad4)") (class "Default")
      (node (ref "U2") (pin "4") (pinfunction "PC15-OSC32_OUT_4") (pintype "passive"))
    )
    (net (code "77") (name "unconnected-(U4-PadA8)") (class "Default")
      (node (ref "U4") (pin "A8") (pinfunction "A8_A8") (pintype "passive+no_connect"))
    )
    (net (code "78") (name "unconnected-(U4-PadB8)") (class "Default")
      (node (ref "U4") (pin "B8") (pinfunction "B8_B8") (pintype "passive+no_connect"))
    )
    (net (code "79") (name "unconnected-(U5-EN-Pad8)") (class "Default")
      (node (ref "U5") (pin "8") (pinfunction "EN_8") (pintype "passive"))
    )
    (net (code "80") (name "unconnected-(U5-NC-Pad1)") (class "Default")
      (node (ref "U5") (pin "1") (pinfunction "NC_1") (pintype "passive"))
    )
  )
)
